# Powermessurment_SCH.net
KiCad netlist of a schematic drawn in Altium Designer
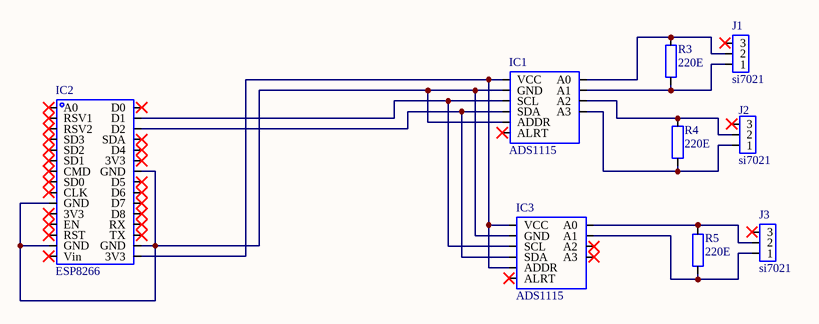
[diagram p0: Powermessurment SCH.schdoc]

(export (version "E")
  (design (tool "Eeschema 10.0.6"))
  (components
    (comp (ref "IC1")
      (value "ADS1115")
      (footprint "ADS1115")
      (libsource (lib "Schemalibary") (part "ADS1115"))
    )
    (comp (ref "IC2")
      (value "ESP8266")
      (footprint "ESP8266")
      (libsource (lib "Schemalibary") (part "ESP8266"))
    )
    (comp (ref "IC3")
      (value "ADS1115")
      (footprint "ADS1115")
      (libsource (lib "Schemalibary") (part "ADS1115"))
    )
    (comp (ref "J1")
      (value "si7021")
      (footprint "3,5mm Jack")
      (libsource (lib "Schemalibary") (part "3,5mm Jack"))
    )
    (comp (ref "J2")
      (value "si7021")
      (footprint "3,5mm Jack")
      (libsource (lib "Schemalibary") (part "3,5mm Jack"))
    )
    (comp (ref "J3")
      (value "si7021")
      (footprint "3,5mm Jack")
      (libsource (lib "Schemalibary") (part "3,5mm Jack"))
    )
    (comp (ref "R3") (value "220E") (footprint "220E") (libsource (lib "Schemalibary") (part "220E")))
    (comp (ref "R4") (value "220E") (footprint "220E") (libsource (lib "Schemalibary") (part "220E")))
    (comp (ref "R5") (value "220E") (footprint "220E") (libsource (lib "Schemalibary") (part "220E")))
  )
  (nets
    (net (code "1") (name "Net-(IC1-A0)") (class "Default")
      (node (ref "IC1") (pin "7") (pinfunction "A0_7") (pintype "passive"))
      (node (ref "J1") (pin "2") (pinfunction "2_2") (pintype "passive"))
      (node (ref "R3") (pin "2") (pintype "passive"))
    )
    (net (code "2") (name "Net-(IC1-A1)") (class "Default")
      (node (ref "IC1") (pin "8") (pinfunction "A1_8") (pintype "passive"))
      (node (ref "J1") (pin "1") (pinfunction "1_1") (pintype "passive"))
      (node (ref "R3") (pin "1") (pinfunction "1_1") (pintype "passive"))
    )
    (net (code "3") (name "Net-(IC1-A2)") (class "Default")
      (node (ref "IC1") (pin "9") (pinfunction "A2_9") (pintype "passive"))
      (node (ref "J2") (pin "2") (pinfunction "2_2") (pintype "passive"))
      (node (ref "R4") (pin "2") (pintype "passive"))
    )
    (net (code "4") (name "Net-(IC1-A3)") (class "Default")
      (node (ref "IC1") (pin "10") (pinfunction "A3_10") (pintype "passive"))
      (node (ref "J2") (pin "1") (pinfunction "1_1") (pintype "passive"))
      (node (ref "R4") (pin "1") (pinfunction "1_1") (pintype "passive"))
    )
    (net (code "5") (name "Net-(IC1-ADDR)") (class "Default")
      (node (ref "IC1") (pin "2") (pinfunction "GND_2") (pintype "passive"))
      (node (ref "IC1") (pin "5") (pinfunction "ADDR_5") (pintype "passive"))
      (node (ref "IC2") (pin "10") (pinfunction "GND_10") (pintype "passive"))
      (node (ref "IC2") (pin "14") (pinfunction "GND_14") (pintype "passive"))
      (node (ref "IC2") (pin "17") (pinfunction "GND_17") (pintype "passive"))
      (node (ref "IC2") (pin "24") (pinfunction "GND_24") (pintype "passive"))
      (node (ref "IC3") (pin "2") (pinfunction "GND_2") (pintype "passive"))
    )
    (net (code "6") (name "Net-(IC1-SCL)") (class "Default")
      (node (ref "IC1") (pin "3") (pinfunction "SCL_3") (pintype "passive"))
      (node (ref "IC2") (pin "29") (pinfunction "D1_29") (pintype "passive"))
      (node (ref "IC3") (pin "3") (pinfunction "SCL_3") (pintype "passive"))
    )
    (net (code "7") (name "Net-(IC1-SDA)") (class "Default")
      (node (ref "IC1") (pin "4") (pinfunction "SDA_4") (pintype "passive"))
      (node (ref "IC2") (pin "28") (pinfunction "D2_28") (pintype "passive"))
      (node (ref "IC3") (pin "4") (pinfunction "SDA_4") (pintype "passive"))
    )
    (net (code "8") (name "Net-(IC1-VCC)") (class "Default")
      (node (ref "IC1") (pin "1") (pinfunction "VCC_1") (pintype "passive"))
      (node (ref "IC2") (pin "16") (pinfunction "3V3_16") (pintype "passive"))
      (node (ref "IC3") (pin "1") (pinfunction "VCC_1") (pintype "passive"))
      (node (ref "IC3") (pin "5") (pinfunction "ADDR_5") (pintype "passive"))
    )
    (net (code "9") (name "Net-(IC3-A0)") (class "Default")
      (node (ref "IC3") (pin "7") (pinfunction "A0_7") (pintype "passive"))
      (node (ref "J3") (pin "2") (pinfunction "2_2") (pintype "passive"))
      (node (ref "R5") (pin "2") (pintype "passive"))
    )
    (net (code "10") (name "Net-(IC3-A1)") (class "Default")
      (node (ref "IC3") (pin "8") (pinfunction "A1_8") (pintype "passive"))
      (node (ref "J3") (pin "1") (pinfunction "1_1") (pintype "passive"))
      (node (ref "R5") (pin "1") (pinfunction "1_1") (pintype "passive"))
    )
    (net (code "11") (name "unconnected-(IC1-ALRT-Pad6)") (class "Default")
      (node (ref "IC1") (pin "6") (pinfunction "ALRT_6") (pintype "passive+no_connect"))
    )
    (net (code "12") (name "unconnected-(IC2-3V3-Pad11)") (class "Default")
      (node (ref "IC2") (pin "11") (pinfunction "3V3_11") (pintype "passive+no_connect"))
    )
    (net (code "13") (name "unconnected-(IC2-3V3-Pad25)") (class "Default")
      (node (ref "IC2") (pin "25") (pinfunction "3V3_25") (pintype "passive+no_connect"))
    )
    (net (code "14") (name "unconnected-(IC2-A0-Pad1)") (class "Default")
      (node (ref "IC2") (pin "1") (pinfunction "A0_1") (pintype "passive+no_connect"))
    )
    (net (code "15") (name "unconnected-(IC2-CLK-Pad9)") (class "Default")
      (node (ref "IC2") (pin "9") (pinfunction "CLK_9") (pintype "passive+no_connect"))
    )
    (net (code "16") (name "unconnected-(IC2-CMD-Pad7)") (class "Default")
      (node (ref "IC2") (pin "7") (pinfunction "CMD_7") (pintype "passive+no_connect"))
    )
    (net (code "17") (name "unconnected-(IC2-D0-Pad30)") (class "Default")
      (node (ref "IC2") (pin "30") (pinfunction "D0_30") (pintype "passive+no_connect"))
    )
    (net (code "18") (name "unconnected-(IC2-D4-Pad26)") (class "Default")
      (node (ref "IC2") (pin "26") (pinfunction "D4_26") (pintype "passive+no_connect"))
    )
    (net (code "19") (name "unconnected-(IC2-D5-Pad23)") (class "Default")
      (node (ref "IC2") (pin "23") (pinfunction "D5_23") (pintype "passive+no_connect"))
    )
    (net (code "20") (name "unconnected-(IC2-D6-Pad22)") (class "Default")
      (node (ref "IC2") (pin "22") (pinfunction "D6_22") (pintype "passive+no_connect"))
    )
    (net (code "21") (name "unconnected-(IC2-D7-Pad21)") (class "Default")
      (node (ref "IC2") (pin "21") (pinfunction "D7_21") (pintype "passive+no_connect"))
    )
    (net (code "22") (name "unconnected-(IC2-D8-Pad20)") (class "Default")
      (node (ref "IC2") (pin "20") (pinfunction "D8_20") (pintype "passive+no_connect"))
    )
    (net (code "23") (name "unconnected-(IC2-EN-Pad12)") (class "Default")
      (node (ref "IC2") (pin "12") (pinfunction "EN_12") (pintype "passive+no_connect"))
    )
    (net (code "24") (name "unconnected-(IC2-RST-Pad13)") (class "Default")
      (node (ref "IC2") (pin "13") (pinfunction "RST_13") (pintype "passive+no_connect"))
    )
    (net (code "25") (name "unconnected-(IC2-RSV1-Pad2)") (class "Default")
      (node (ref "IC2") (pin "2") (pinfunction "RSV1_2") (pintype "passive+no_connect"))
    )
    (net (code "26") (name "unconnected-(IC2-RSV2-Pad3)") (class "Default")
      (node (ref "IC2") (pin "3") (pinfunction "RSV2_3") (pintype "passive+no_connect"))
    )
    (net (code "27") (name "unconnected-(IC2-RX-Pad19)") (class "Default")
      (node (ref "IC2") (pin "19") (pinfunction "RX_19") (pintype "passive+no_connect"))
    )
    (net (code "28") (name "unconnected-(IC2-SD0-Pad8)") (class "Default")
      (node (ref "IC2") (pin "8") (pinfunction "SD0_8") (pintype "passive+no_connect"))
    )
    (net (code "29") (name "unconnected-(IC2-SD1-Pad6)") (class "Default")
      (node (ref "IC2") (pin "6") (pinfunction "SD1_6") (pintype "passive+no_connect"))
    )
    (net (code "30") (name "unconnected-(IC2-SD2-Pad5)") (class "Default")
      (node (ref "IC2") (pin "5") (pinfunction "SD2_5") (pintype "passive+no_connect"))
    )
    (net (code "31") (name "unconnected-(IC2-SD3-Pad4)") (class "Default")
      (node (ref "IC2") (pin "4") (pinfunction "SD3_4") (pintype "passive+no_connect"))
    )
    (net (code "32") (name "unconnected-(IC2-SDA-Pad27)") (class "Default")
      (node (ref "IC2") (pin "27") (pinfunction "SDA_27") (pintype "passive+no_connect"))
    )
    (net (code "33") (name "unconnected-(IC2-TX-Pad18)") (class "Default")
      (node (ref "IC2") (pin "18") (pinfunction "TX_18") (pintype "passive+no_connect"))
    )
    (net (code "34") (name "unconnected-(IC2-Vin-Pad15)") (class "Default")
      (node (ref "IC2") (pin "15") (pinfunction "Vin_15") (pintype "passive+no_connect"))
    )
    (net (code "35") (name "unconnected-(IC3-A2-Pad9)") (class "Default")
      (node (ref "IC3") (pin "9") (pinfunction "A2_9") (pintype "passive+no_connect"))
    )
    (net (code "36") (name "unconnected-(IC3-A3-Pad10)") (class "Default")
      (node (ref "IC3") (pin "10") (pinfunction "A3_10") (pintype "passive+no_connect"))
    )
    (net (code "37") (name "unconnected-(IC3-ALRT-Pad6)") (class "Default")
      (node (ref "IC3") (pin "6") (pinfunction "ALRT_6") (pintype "passive+no_connect"))
    )
    (net (code "38") (name "unconnected-(J1-Pad3)") (class "Default")
      (node (ref "J1") (pin "3") (pinfunction "3_3") (pintype "passive+no_connect"))
    )
    (net (code "39") (name "unconnected-(J2-Pad3)") (class "Default")
      (node (ref "J2") (pin "3") (pinfunction "3_3") (pintype "passive+no_connect"))
    )
    (net (code "40") (name "unconnected-(J3-Pad3)") (class "Default")
      (node (ref "J3") (pin "3") (pinfunction "3_3") (pintype "passive+no_connect"))
    )
  )
)
